# Schematic.net
KiCad netlist of a schematic drawn in Altium Designer
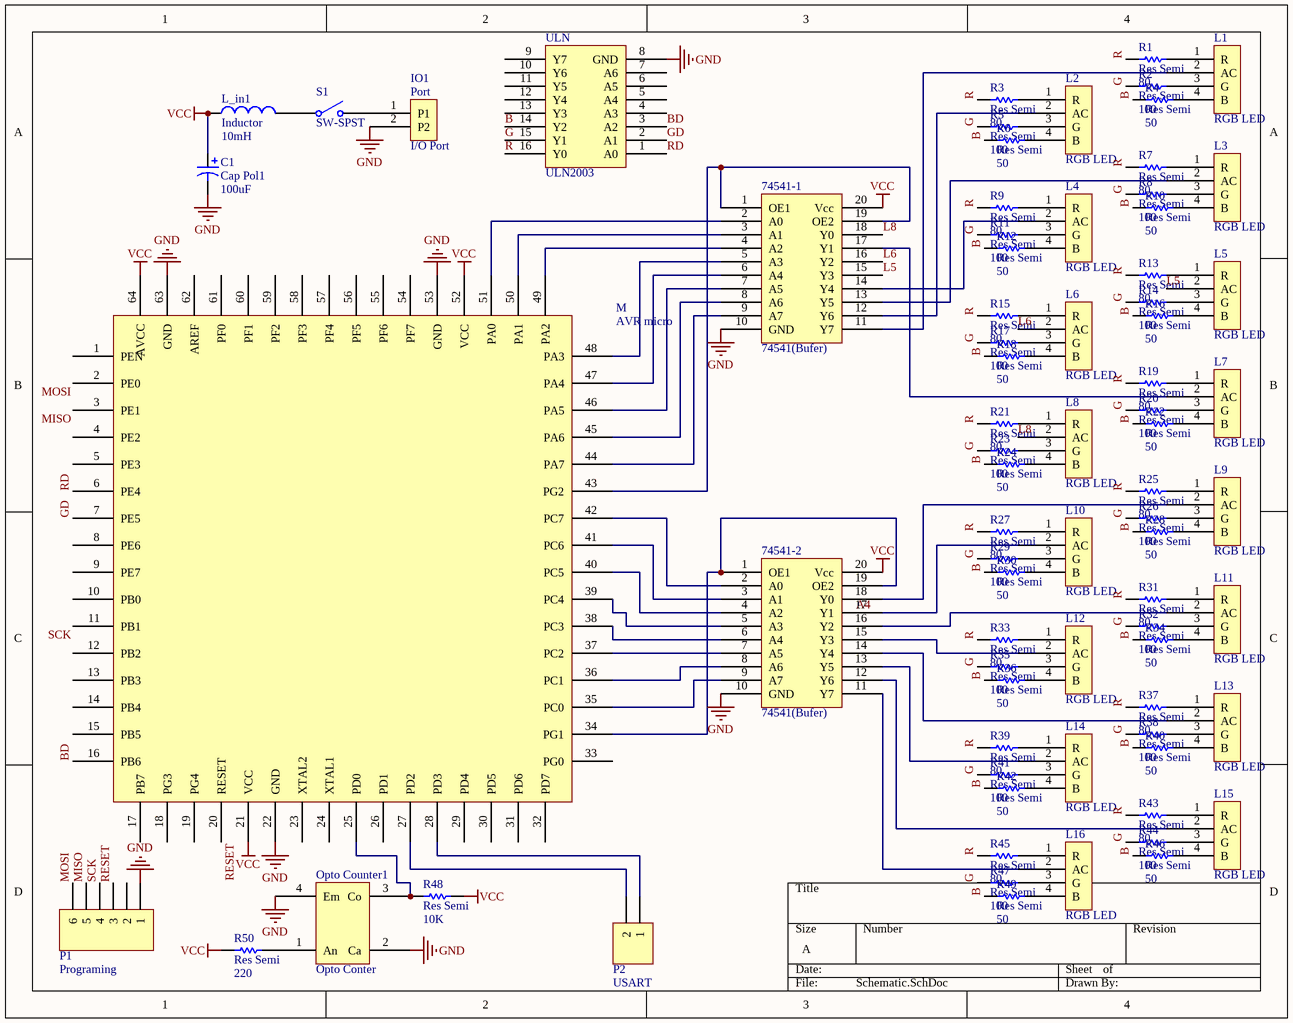
[diagram p0: Schematic.SchDoc]

(export (version "E")
  (design (tool "Eeschema 10.0.6"))
  (components
    (comp (ref "74541-1")
      (value "74541(Bufer)")
      (footprint "SOT146-1")
      (libsource (lib "Schematic Library") (part "74541(Bufer)"))
    )
    (comp (ref "74541-2")
      (value "74541(Bufer)")
      (footprint "SOT146-1")
      (libsource (lib "Schematic Library") (part "74541(Bufer)"))
    )
    (comp (ref "C1")
      (value "Cap Pol1")
      (footprint "CAPPR5-5x5")
      (description "Polarized Capacitor (Radial)")
      (fields (field (name "ALTIUM_VALUE") "100uF") (field (name "PUBLISHER") "Altium Limited"))
      (libsource (lib "Miscellaneous Devices") (part "Cap Pol1"))
    )
    (comp (ref "IO1")
      (value "I/O Port")
      (footprint "I/O")
      (libsource (lib "Schematic Library") (part "I/O Port"))
    )
    (comp (ref "L1")
      (value "RGB LED")
      (footprint "RGB LED")
      (libsource (lib "Schematic Library") (part "RGB LED"))
    )
    (comp (ref "L2")
      (value "RGB LED")
      (footprint "RGB LED")
      (libsource (lib "Schematic Library") (part "RGB LED"))
    )
    (comp (ref "L3")
      (value "RGB LED")
      (footprint "RGB LED")
      (libsource (lib "Schematic Library") (part "RGB LED"))
    )
    (comp (ref "L4")
      (value "RGB LED")
      (footprint "RGB LED")
      (libsource (lib "Schematic Library") (part "RGB LED"))
    )
    (comp (ref "L5")
      (value "RGB LED")
      (footprint "RGB LED")
      (libsource (lib "Schematic Library") (part "RGB LED"))
    )
    (comp (ref "L6")
      (value "RGB LED")
      (footprint "RGB LED")
      (libsource (lib "Schematic Library") (part "RGB LED"))
    )
    (comp (ref "L7")
      (value "RGB LED")
      (footprint "RGB LED")
      (libsource (lib "Schematic Library") (part "RGB LED"))
    )
    (comp (ref "L8")
      (value "RGB LED")
      (footprint "RGB LED")
      (libsource (lib "Schematic Library") (part "RGB LED"))
    )
    (comp (ref "L9")
      (value "RGB LED")
      (footprint "RGB LED")
      (libsource (lib "Schematic Library") (part "RGB LED"))
    )
    (comp (ref "L10")
      (value "RGB LED")
      (footprint "RGB LED")
      (libsource (lib "Schematic Library") (part "RGB LED"))
    )
    (comp (ref "L11")
      (value "RGB LED")
      (footprint "RGB LED")
      (libsource (lib "Schematic Library") (part "RGB LED"))
    )
    (comp (ref "L12")
      (value "RGB LED")
      (footprint "RGB LED")
      (libsource (lib "Schematic Library") (part "RGB LED"))
    )
    (comp (ref "L13")
      (value "RGB LED")
      (footprint "RGB LED")
      (libsource (lib "Schematic Library") (part "RGB LED"))
    )
    (comp (ref "L14")
      (value "RGB LED")
      (footprint "RGB LED")
      (libsource (lib "Schematic Library") (part "RGB LED"))
    )
    (comp (ref "L15")
      (value "RGB LED")
      (footprint "RGB LED")
      (libsource (lib "Schematic Library") (part "RGB LED"))
    )
    (comp (ref "L16")
      (value "RGB LED")
      (footprint "RGB LED")
      (libsource (lib "Schematic Library") (part "RGB LED"))
    )
    (comp (ref "L_in1")
      (value "Inductor")
      (footprint "AXIAL-0.8")
      (fields (field (name "ALTIUM_VALUE") "10mH") (field (name "PUBLISHER") "Altium Limited"))
      (libsource (lib "Miscellaneous Devices") (part "Inductor"))
    )
    (comp (ref "M")
      (value "AVR micro")
      (footprint "64A_M")
      (libsource (lib "Schematic Library") (part "ATmega64"))
    )
    (comp (ref "Opto Counter1")
      (value "Opto Conter")
      (footprint "Opto Counter")
      (libsource (lib "Schematic Library") (part "Opto Counter"))
    )
    (comp (ref "P1")
      (value "Programing")
      (footprint "HDR1X6")
      (description "Header, 6-Pin")
      (fields (field (name "PUBLISHER") "Altium Limited"))
      (libsource (lib "Miscellaneous Connectors") (part "Header 6"))
    )
    (comp (ref "P2")
      (value "USART")
      (footprint "HDR1X2")
      (description "Header, 2-Pin")
      (fields (field (name "PUBLISHER") "Altium Limited"))
      (libsource (lib "Miscellaneous Connectors") (part "Header 2"))
    )
    (comp (ref "R1")
      (value "Res Semi")
      (footprint "RESC2012L")
      (description "Semiconductor Resistor")
      (fields (field (name "ALTIUM_VALUE") "80") (field (name "PUBLISHER") "Altium Limited"))
      (libsource (lib "Miscellaneous Devices") (part "Res Semi"))
    )
    (comp (ref "R2")
      (value "Res Semi")
      (footprint "RESC2012L")
      (description "Semiconductor Resistor")
      (fields (field (name "ALTIUM_VALUE") "100") (field (name "PUBLISHER") "Altium Limited"))
      (libsource (lib "Miscellaneous Devices") (part "Res Semi"))
    )
    (comp (ref "R3")
      (value "Res Semi")
      (footprint "RESC2012L")
      (description "Semiconductor Resistor")
      (fields (field (name "ALTIUM_VALUE") "80") (field (name "PUBLISHER") "Altium Limited"))
      (libsource (lib "Miscellaneous Devices") (part "Res Semi"))
    )
    (comp (ref "R4")
      (value "Res Semi")
      (footprint "RESC2012L")
      (description "Semiconductor Resistor")
      (fields (field (name "ALTIUM_VALUE") "50") (field (name "PUBLISHER") "Altium Limited"))
      (libsource (lib "Miscellaneous Devices") (part "Res Semi"))
    )
    (comp (ref "R5")
      (value "Res Semi")
      (footprint "RESC2012L")
      (description "Semiconductor Resistor")
      (fields (field (name "ALTIUM_VALUE") "100") (field (name "PUBLISHER") "Altium Limited"))
      (libsource (lib "Miscellaneous Devices") (part "Res Semi"))
    )
    (comp (ref "R6")
      (value "Res Semi")
      (footprint "RESC2012L")
      (description "Semiconductor Resistor")
      (fields (field (name "ALTIUM_VALUE") "50") (field (name "PUBLISHER") "Altium Limited"))
      (libsource (lib "Miscellaneous Devices") (part "Res Semi"))
    )
    (comp (ref "R7")
      (value "Res Semi")
      (footprint "RESC2012L")
      (description "Semiconductor Resistor")
      (fields (field (name "ALTIUM_VALUE") "80") (field (name "PUBLISHER") "Altium Limited"))
      (libsource (lib "Miscellaneous Devices") (part "Res Semi"))
    )
    (comp (ref "R8")
      (value "Res Semi")
      (footprint "RESC2012L")
      (description "Semiconductor Resistor")
      (fields (field (name "ALTIUM_VALUE") "100") (field (name "PUBLISHER") "Altium Limited"))
      (libsource (lib "Miscellaneous Devices") (part "Res Semi"))
    )
    (comp (ref "R9")
      (value "Res Semi")
      (footprint "RESC2012L")
      (description "Semiconductor Resistor")
      (fields (field (name "ALTIUM_VALUE") "80") (field (name "PUBLISHER") "Altium Limited"))
      (libsource (lib "Miscellaneous Devices") (part "Res Semi"))
    )
    (comp (ref "R10")
      (value "Res Semi")
      (footprint "RESC2012L")
      (description "Semiconductor Resistor")
      (fields (field (name "ALTIUM_VALUE") "50") (field (name "PUBLISHER") "Altium Limited"))
      (libsource (lib "Miscellaneous Devices") (part "Res Semi"))
    )
    (comp (ref "R11")
      (value "Res Semi")
      (footprint "RESC2012L")
      (description "Semiconductor Resistor")
      (fields (field (name "ALTIUM_VALUE") "100") (field (name "PUBLISHER") "Altium Limited"))
      (libsource (lib "Miscellaneous Devices") (part "Res Semi"))
    )
    (comp (ref "R12")
      (value "Res Semi")
      (footprint "RESC2012L")
      (description "Semiconductor Resistor")
      (fields (field (name "ALTIUM_VALUE") "50") (field (name "PUBLISHER") "Altium Limited"))
      (libsource (lib "Miscellaneous Devices") (part "Res Semi"))
    )
    (comp (ref "R13")
      (value "Res Semi")
      (footprint "RESC2012L")
      (description "Semiconductor Resistor")
      (fields (field (name "ALTIUM_VALUE") "80") (field (name "PUBLISHER") "Altium Limited"))
      (libsource (lib "Miscellaneous Devices") (part "Res Semi"))
    )
    (comp (ref "R14")
      (value "Res Semi")
      (footprint "RESC2012L")
      (description "Semiconductor Resistor")
      (fields (field (name "ALTIUM_VALUE") "100") (field (name "PUBLISHER") "Altium Limited"))
      (libsource (lib "Miscellaneous Devices") (part "Res Semi"))
    )
    (comp (ref "R15")
      (value "Res Semi")
      (footprint "RESC2012L")
      (description "Semiconductor Resistor")
      (fields (field (name "ALTIUM_VALUE") "80") (field (name "PUBLISHER") "Altium Limited"))
      (libsource (lib "Miscellaneous Devices") (part "Res Semi"))
    )
    (comp (ref "R16")
      (value "Res Semi")
      (footprint "RESC2012L")
      (description "Semiconductor Resistor")
      (fields (field (name "ALTIUM_VALUE") "50") (field (name "PUBLISHER") "Altium Limited"))
      (libsource (lib "Miscellaneous Devices") (part "Res Semi"))
    )
    (comp (ref "R17")
      (value "Res Semi")
      (footprint "RESC2012L")
      (description "Semiconductor Resistor")
      (fields (field (name "ALTIUM_VALUE") "100") (field (name "PUBLISHER") "Altium Limited"))
      (libsource (lib "Miscellaneous Devices") (part "Res Semi"))
    )
    (comp (ref "R18")
      (value "Res Semi")
      (footprint "RESC2012L")
      (description "Semiconductor Resistor")
      (fields (field (name "ALTIUM_VALUE") "50") (field (name "PUBLISHER") "Altium Limited"))
      (libsource (lib "Miscellaneous Devices") (part "Res Semi"))
    )
    (comp (ref "R19")
      (value "Res Semi")
      (footprint "RESC2012L")
      (description "Semiconductor Resistor")
      (fields (field (name "ALTIUM_VALUE") "80") (field (name "PUBLISHER") "Altium Limited"))
      (libsource (lib "Miscellaneous Devices") (part "Res Semi"))
    )
    (comp (ref "R20")
      (value "Res Semi")
      (footprint "RESC2012L")
      (description "Semiconductor Resistor")
      (fields (field (name "ALTIUM_VALUE") "100") (field (name "PUBLISHER") "Altium Limited"))
      (libsource (lib "Miscellaneous Devices") (part "Res Semi"))
    )
    (comp (ref "R21")
      (value "Res Semi")
      (footprint "RESC2012L")
      (description "Semiconductor Resistor")
      (fields (field (name "ALTIUM_VALUE") "80") (field (name "PUBLISHER") "Altium Limited"))
      (libsource (lib "Miscellaneous Devices") (part "Res Semi"))
    )
    (comp (ref "R22")
      (value "Res Semi")
      (footprint "RESC2012L")
      (description "Semiconductor Resistor")
      (fields (field (name "ALTIUM_VALUE") "50") (field (name "PUBLISHER") "Altium Limited"))
      (libsource (lib "Miscellaneous Devices") (part "Res Semi"))
    )
    (comp (ref "R23")
      (value "Res Semi")
      (footprint "RESC2012L")
      (description "Semiconductor Resistor")
      (fields (field (name "ALTIUM_VALUE") "100") (field (name "PUBLISHER") "Altium Limited"))
      (libsource (lib "Miscellaneous Devices") (part "Res Semi"))
    )
    (comp (ref "R24")
      (value "Res Semi")
      (footprint "RESC2012L")
      (description "Semiconductor Resistor")
      (fields (field (name "ALTIUM_VALUE") "50") (field (name "PUBLISHER") "Altium Limited"))
      (libsource (lib "Miscellaneous Devices") (part "Res Semi"))
    )
    (comp (ref "R25")
      (value "Res Semi")
      (footprint "RESC2012L")
      (description "Semiconductor Resistor")
      (fields (field (name "ALTIUM_VALUE") "80") (field (name "PUBLISHER") "Altium Limited"))
      (libsource (lib "Miscellaneous Devices") (part "Res Semi"))
    )
    (comp (ref "R26")
      (value "Res Semi")
      (footprint "RESC2012L")
      (description "Semiconductor Resistor")
      (fields (field (name "ALTIUM_VALUE") "100") (field (name "PUBLISHER") "Altium Limited"))
      (libsource (lib "Miscellaneous Devices") (part "Res Semi"))
    )
    (comp (ref "R27")
      (value "Res Semi")
      (footprint "RESC2012L")
      (description "Semiconductor Resistor")
      (fields (field (name "ALTIUM_VALUE") "80") (field (name "PUBLISHER") "Altium Limited"))
      (libsource (lib "Miscellaneous Devices") (part "Res Semi"))
    )
    (comp (ref "R28")
      (value "Res Semi")
      (footprint "RESC2012L")
      (description "Semiconductor Resistor")
      (fields (field (name "ALTIUM_VALUE") "50") (field (name "PUBLISHER") "Altium Limited"))
      (libsource (lib "Miscellaneous Devices") (part "Res Semi"))
    )
    (comp (ref "R29")
      (value "Res Semi")
      (footprint "RESC2012L")
      (description "Semiconductor Resistor")
      (fields (field (name "ALTIUM_VALUE") "100") (field (name "PUBLISHER") "Altium Limited"))
      (libsource (lib "Miscellaneous Devices") (part "Res Semi"))
    )
    (comp (ref "R30")
      (value "Res Semi")
      (footprint "RESC2012L")
      (description "Semiconductor Resistor")
      (fields (field (name "ALTIUM_VALUE") "50") (field (name "PUBLISHER") "Altium Limited"))
      (libsource (lib "Miscellaneous Devices") (part "Res Semi"))
    )
    (comp (ref "R31")
      (value "Res Semi")
      (footprint "RESC2012L")
      (description "Semiconductor Resistor")
      (fields (field (name "ALTIUM_VALUE") "80") (field (name "PUBLISHER") "Altium Limited"))
      (libsource (lib "Miscellaneous Devices") (part "Res Semi"))
    )
    (comp (ref "R32")
      (value "Res Semi")
      (footprint "RESC2012L")
      (description "Semiconductor Resistor")
      (fields (field (name "ALTIUM_VALUE") "100") (field (name "PUBLISHER") "Altium Limited"))
      (libsource (lib "Miscellaneous Devices") (part "Res Semi"))
    )
    (comp (ref "R33")
      (value "Res Semi")
      (footprint "RESC2012L")
      (description "Semiconductor Resistor")
      (fields (field (name "ALTIUM_VALUE") "80") (field (name "PUBLISHER") "Altium Limited"))
      (libsource (lib "Miscellaneous Devices") (part "Res Semi"))
    )
    (comp (ref "R34")
      (value "Res Semi")
      (footprint "RESC2012L")
      (description "Semiconductor Resistor")
      (fields (field (name "ALTIUM_VALUE") "50") (field (name "PUBLISHER") "Altium Limited"))
      (libsource (lib "Miscellaneous Devices") (part "Res Semi"))
    )
    (comp (ref "R35")
      (value "Res Semi")
      (footprint "RESC2012L")
      (description "Semiconductor Resistor")
      (fields (field (name "ALTIUM_VALUE") "100") (field (name "PUBLISHER") "Altium Limited"))
      (libsource (lib "Miscellaneous Devices") (part "Res Semi"))
    )
    (comp (ref "R36")
      (value "Res Semi")
      (footprint "RESC2012L")
      (description "Semiconductor Resistor")
      (fields (field (name "ALTIUM_VALUE") "50") (field (name "PUBLISHER") "Altium Limited"))
      (libsource (lib "Miscellaneous Devices") (part "Res Semi"))
    )
    (comp (ref "R37")
      (value "Res Semi")
      (footprint "RESC2012L")
      (description "Semiconductor Resistor")
      (fields (field (name "ALTIUM_VALUE") "80") (field (name "PUBLISHER") "Altium Limited"))
      (libsource (lib "Miscellaneous Devices") (part "Res Semi"))
    )
    (comp (ref "R38")
      (value "Res Semi")
      (footprint "RESC2012L")
      (description "Semiconductor Resistor")
      (fields (field (name "ALTIUM_VALUE") "100") (field (name "PUBLISHER") "Altium Limited"))
      (libsource (lib "Miscellaneous Devices") (part "Res Semi"))
    )
    (comp (ref "R39")
      (value "Res Semi")
      (footprint "RESC2012L")
      (description "Semiconductor Resistor")
      (fields (field (name "ALTIUM_VALUE") "80") (field (name "PUBLISHER") "Altium Limited"))
      (libsource (lib "Miscellaneous Devices") (part "Res Semi"))
    )
    (comp (ref "R40")
      (value "Res Semi")
      (footprint "RESC2012L")
      (description "Semiconductor Resistor")
      (fields (field (name "ALTIUM_VALUE") "50") (field (name "PUBLISHER") "Altium Limited"))
      (libsource (lib "Miscellaneous Devices") (part "Res Semi"))
    )
    (comp (ref "R41")
      (value "Res Semi")
      (footprint "RESC2012L")
      (description "Semiconductor Resistor")
      (fields (field (name "ALTIUM_VALUE") "100") (field (name "PUBLISHER") "Altium Limited"))
      (libsource (lib "Miscellaneous Devices") (part "Res Semi"))
    )
    (comp (ref "R42")
      (value "Res Semi")
      (footprint "RESC2012L")
      (description "Semiconductor Resistor")
      (fields (field (name "ALTIUM_VALUE") "50") (field (name "PUBLISHER") "Altium Limited"))
      (libsource (lib "Miscellaneous Devices") (part "Res Semi"))
    )
    (comp (ref "R43")
      (value "Res Semi")
      (footprint "RESC2012L")
      (description "Semiconductor Resistor")
      (fields (field (name "ALTIUM_VALUE") "80") (field (name "PUBLISHER") "Altium Limited"))
      (libsource (lib "Miscellaneous Devices") (part "Res Semi"))
    )
    (comp (ref "R44")
      (value "Res Semi")
      (footprint "RESC2012L")
      (description "Semiconductor Resistor")
      (fields (field (name "ALTIUM_VALUE") "100") (field (name "PUBLISHER") "Altium Limited"))
      (libsource (lib "Miscellaneous Devices") (part "Res Semi"))
    )
    (comp (ref "R45")
      (value "Res Semi")
      (footprint "RESC2012L")
      (description "Semiconductor Resistor")
      (fields (field (name "ALTIUM_VALUE") "80") (field (name "PUBLISHER") "Altium Limited"))
      (libsource (lib "Miscellaneous Devices") (part "Res Semi"))
    )
    (comp (ref "R46")
      (value "Res Semi")
      (footprint "RESC2012L")
      (description "Semiconductor Resistor")
      (fields (field (name "ALTIUM_VALUE") "50") (field (name "PUBLISHER") "Altium Limited"))
      (libsource (lib "Miscellaneous Devices") (part "Res Semi"))
    )
    (comp (ref "R47")
      (value "Res Semi")
      (footprint "RESC2012L")
      (description "Semiconductor Resistor")
      (fields (field (name "ALTIUM_VALUE") "100") (field (name "PUBLISHER") "Altium Limited"))
      (libsource (lib "Miscellaneous Devices") (part "Res Semi"))
    )
    (comp (ref "R48")
      (value "Res Semi")
      (footprint "RESC2012L")
      (description "Semiconductor Resistor")
      (fields (field (name "ALTIUM_VALUE") "10K") (field (name "PUBLISHER") "Altium Limited"))
      (libsource (lib "Miscellaneous Devices") (part "Res Semi"))
    )
    (comp (ref "R49")
      (value "Res Semi")
      (footprint "RESC2012L")
      (description "Semiconductor Resistor")
      (fields (field (name "ALTIUM_VALUE") "50") (field (name "PUBLISHER") "Altium Limited"))
      (libsource (lib "Miscellaneous Devices") (part "Res Semi"))
    )
    (comp (ref "R50")
      (value "Res Semi")
      (footprint "RESC2012L")
      (description "Semiconductor Resistor")
      (fields (field (name "ALTIUM_VALUE") "220") (field (name "PUBLISHER") "Altium Limited"))
      (libsource (lib "Miscellaneous Devices") (part "Res Semi"))
    )
    (comp (ref "S1")
      (value "SW-SPST")
      (footprint "SPST-2")
      (description "Single-Pole, Single-Throw Switch")
      (fields (field (name "PUBLISHER") "Altium Limited"))
      (libsource (lib "Miscellaneous Devices") (part "SW-SPST"))
    )
    (comp (ref "ULN")
      (value "ULN2003")
      (footprint "A16")
      (libsource (lib "Schematic Library") (part "ULN2003"))
    )
  )
  (nets
    (net (code "2") (name "/B") (class "Default")
      (node (ref "R10") (pin "1") (pinfunction "1_1") (pintype "passive"))
      (node (ref "R12") (pin "1") (pinfunction "1_1") (pintype "passive"))
      (node (ref "R16") (pin "1") (pinfunction "1_1") (pintype "passive"))
      (node (ref "R18") (pin "1") (pinfunction "1_1") (pintype "passive"))
      (node (ref "R22") (pin "1") (pinfunction "1_1") (pintype "passive"))
      (node (ref "R24") (pin "1") (pinfunction "1_1") (pintype "passive"))
      (node (ref "R28") (pin "1") (pinfunction "1_1") (pintype "passive"))
      (node (ref "R30") (pin "1") (pinfunction "1_1") (pintype "passive"))
      (node (ref "R34") (pin "1") (pinfunction "1_1") (pintype "passive"))
      (node (ref "R36") (pin "1") (pinfunction "1_1") (pintype "passive"))
      (node (ref "R4") (pin "1") (pinfunction "1_1") (pintype "passive"))
      (node (ref "R40") (pin "1") (pinfunction "1_1") (pintype "passive"))
      (node (ref "R42") (pin "1") (pinfunction "1_1") (pintype "passive"))
      (node (ref "R46") (pin "1") (pinfunction "1_1") (pintype "passive"))
      (node (ref "R49") (pin "1") (pinfunction "1_1") (pintype "passive"))
      (node (ref "R6") (pin "1") (pinfunction "1_1") (pintype "passive"))
      (node (ref "ULN") (pin "14") (pinfunction "Y2_14") (pintype "passive"))
    )
    (net (code "3") (name "/BD") (class "Default")
      (node (ref "M") (pin "16") (pinfunction "PB6_16") (pintype "passive"))
      (node (ref "ULN") (pin "3") (pinfunction "A2_3") (pintype "passive"))
    )
    (net (code "4") (name "/G") (class "Default")
      (node (ref "R11") (pin "1") (pinfunction "1_1") (pintype "passive"))
      (node (ref "R14") (pin "1") (pinfunction "1_1") (pintype "passive"))
      (node (ref "R17") (pin "1") (pinfunction "1_1") (pintype "passive"))
      (node (ref "R2") (pin "1") (pinfunction "1_1") (pintype "passive"))
      (node (ref "R20") (pin "1") (pinfunction "1_1") (pintype "passive"))
      (node (ref "R23") (pin "1") (pinfunction "1_1") (pintype "passive"))
      (node (ref "R26") (pin "1") (pinfunction "1_1") (pintype "passive"))
      (node (ref "R29") (pin "1") (pinfunction "1_1") (pintype "passive"))
      (node (ref "R32") (pin "1") (pinfunction "1_1") (pintype "passive"))
      (node (ref "R35") (pin "1") (pinfunction "1_1") (pintype "passive"))
      (node (ref "R38") (pin "1") (pinfunction "1_1") (pintype "passive"))
      (node (ref "R41") (pin "1") (pinfunction "1_1") (pintype "passive"))
      (node (ref "R44") (pin "1") (pinfunction "1_1") (pintype "passive"))
      (node (ref "R47") (pin "1") (pinfunction "1_1") (pintype "passive"))
      (node (ref "R5") (pin "1") (pinfunction "1_1") (pintype "passive"))
      (node (ref "R8") (pin "1") (pinfunction "1_1") (pintype "passive"))
      (node (ref "ULN") (pin "15") (pinfunction "Y1_15") (pintype "passive"))
    )
    (net (code "5") (name "/GD") (class "Default")
      (node (ref "M") (pin "7") (pinfunction "PE5_7") (pintype "passive"))
      (node (ref "ULN") (pin "2") (pinfunction "A1_2") (pintype "passive"))
    )
    (net (code "6") (name "/L5") (class "Default")
      (node (ref "74541-1") (pin "15") (pinfunction "Y3_15") (pintype "passive"))
      (node (ref "L5") (pin "2") (pinfunction "AC_2") (pintype "passive"))
    )
    (net (code "7") (name "/L6") (class "Default")
      (node (ref "74541-1") (pin "16") (pinfunction "Y2_16") (pintype "passive"))
      (node (ref "L6") (pin "2") (pinfunction "AC_2") (pintype "passive"))
    )
    (net (code "8") (name "/L8") (class "Default")
      (node (ref "74541-1") (pin "18") (pinfunction "Y0_18") (pintype "passive"))
      (node (ref "L8") (pin "2") (pinfunction "AC_2") (pintype "passive"))
    )
    (net (code "9") (name "/MISO") (class "Default")
      (node (ref "M") (pin "3") (pinfunction "PE1_3") (pintype "passive"))
      (node (ref "P1") (pin "5") (pinfunction "5_5") (pintype "passive"))
    )
    (net (code "10") (name "/MOSI") (class "Default")
      (node (ref "M") (pin "2") (pinfunction "PE0_2") (pintype "passive"))
      (node (ref "P1") (pin "6") (pinfunction "6_6") (pintype "passive"))
    )
    (net (code "11") (name "/R") (class "Default")
      (node (ref "R1") (pin "1") (pinfunction "1_1") (pintype "passive"))
      (node (ref "R13") (pin "1") (pinfunction "1_1") (pintype "passive"))
      (node (ref "R15") (pin "1") (pinfunction "1_1") (pintype "passive"))
      (node (ref "R19") (pin "1") (pinfunction "1_1") (pintype "passive"))
      (node (ref "R21") (pin "1") (pinfunction "1_1") (pintype "passive"))
      (node (ref "R25") (pin "1") (pinfunction "1_1") (pintype "passive"))
      (node (ref "R27") (pin "1") (pinfunction "1_1") (pintype "passive"))
      (node (ref "R3") (pin "1") (pinfunction "1_1") (pintype "passive"))
      (node (ref "R31") (pin "1") (pinfunction "1_1") (pintype "passive"))
      (node (ref "R33") (pin "1") (pinfunction "1_1") (pintype "passive"))
      (node (ref "R37") (pin "1") (pinfunction "1_1") (pintype "passive"))
      (node (ref "R39") (pin "1") (pinfunction "1_1") (pintype "passive"))
      (node (ref "R43") (pin "1") (pinfunction "1_1") (pintype "passive"))
      (node (ref "R45") (pin "1") (pinfunction "1_1") (pintype "passive"))
      (node (ref "R7") (pin "1") (pinfunction "1_1") (pintype "passive"))
      (node (ref "R9") (pin "1") (pinfunction "1_1") (pintype "passive"))
      (node (ref "ULN") (pin "16") (pinfunction "Y0_16") (pintype "passive"))
    )
    (net (code "12") (name "/RD") (class "Default")
      (node (ref "M") (pin "6") (pinfunction "PE4_6") (pintype "passive"))
      (node (ref "ULN") (pin "1") (pinfunction "A0_1") (pintype "passive"))
    )
    (net (code "13") (name "/RESET") (class "Default")
      (node (ref "M") (pin "20") (pinfunction "RESET_20") (pintype "passive"))
      (node (ref "P1") (pin "3") (pinfunction "3_3") (pintype "passive"))
    )
    (net (code "14") (name "/SCK") (class "Default")
      (node (ref "M") (pin "11") (pinfunction "PB1_11") (pintype "passive"))
      (node (ref "P1") (pin "4") (pinfunction "4_4") (pintype "passive"))
    )
    (net (code "15") (name "GND") (class "Default")
      (node (ref "74541-1") (pin "10") (pinfunction "GND_10") (pintype "passive"))
      (node (ref "74541-2") (pin "10") (pinfunction "GND_10") (pintype "passive"))
      (node (ref "C1") (pin "2") (pinfunction "2_2") (pintype "passive"))
      (node (ref "IO1") (pin "2") (pinfunction "P2_2") (pintype "passive"))
      (node (ref "M") (pin "22") (pinfunction "GND_22") (pintype "power_in"))
      (node (ref "M") (pin "53") (pinfunction "GND_53") (pintype "power_in"))
      (node (ref "M") (pin "63") (pinfunction "GND_63") (pintype "power_in"))
      (node (ref "Opto Counter1") (pin "2") (pinfunction "Ca_2") (pintype "passive"))
      (node (ref "Opto Counter1") (pin "4") (pinfunction "Em_4") (pintype "passive"))
      (node (ref "P1") (pin "1") (pinfunction "1_1") (pintype "passive"))
      (node (ref "ULN") (pin "8") (pinfunction "GND_8") (pintype "passive"))
    )
    (net (code "16") (name "Net-(74541-1-A0)") (class "Default")
      (node (ref "74541-1") (pin "2") (pinfunction "A0_2") (pintype "passive"))
      (node (ref "M") (pin "51") (pinfunction "PA0_51") (pintype "passive"))
    )
    (net (code "17") (name "Net-(74541-1-A1)") (class "Default")
      (node (ref "74541-1") (pin "3") (pinfunction "A1_3") (pintype "passive"))
      (node (ref "M") (pin "50") (pinfunction "PA1_50") (pintype "passive"))
    )
    (net (code "18") (name "Net-(74541-1-A2)") (class "Default")
      (node (ref "74541-1") (pin "4") (pinfunction "A2_4") (pintype "passive"))
      (node (ref "M") (pin "49") (pinfunction "PA2_49") (pintype "passive"))
    )
    (net (code "19") (name "Net-(74541-1-A3)") (class "Default")
      (node (ref "74541-1") (pin "5") (pinfunction "A3_5") (pintype "passive"))
      (node (ref "M") (pin "48") (pinfunction "PA3_48") (pintype "passive"))
    )
    (net (code "20") (name "Net-(74541-1-A4)") (class "Default")
      (node (ref "74541-1") (pin "6") (pinfunction "A4_6") (pintype "passive"))
      (node (ref "M") (pin "47") (pinfunction "PA4_47") (pintype "passive"))
    )
    (net (code "21") (name "Net-(74541-1-A5)") (class "Default")
      (node (ref "74541-1") (pin "7") (pinfunction "A5_7") (pintype "passive"))
      (node (ref "M") (pin "46") (pinfunction "PA5_46") (pintype "passive"))
    )
    (net (code "22") (name "Net-(74541-1-A6)") (class "Default")
      (node (ref "74541-1") (pin "8") (pinfunction "A6_8") (pintype "passive"))
      (node (ref "M") (pin "45") (pinfunction "PA6_45") (pintype "passive"))
    )
    (net (code "23") (name "Net-(74541-1-A7)") (class "Default")
      (node (ref "74541-1") (pin "9") (pinfunction "A7_9") (pintype "passive"))
      (node (ref "M") (pin "44") (pinfunction "PA7_44") (pintype "passive"))
    )
    (net (code "24") (name "Net-(74541-1-OE1)") (class "Default")
      (node (ref "74541-1") (pin "1") (pinfunction "OE1_1") (pintype "passive"))
      (node (ref "74541-1") (pin "19") (pinfunction "OE2_19") (pintype "passive"))
      (node (ref "M") (pin "43") (pinfunction "PG2_43") (pintype "passive"))
    )
    (net (code "25") (name "Net-(74541-1-Y1)") (class "Default")
      (node (ref "74541-1") (pin "17") (pinfunction "Y1_17") (pintype "passive"))
      (node (ref "L7") (pin "2") (pinfunction "AC_2") (pintype "passive"))
    )
    (net (code "26") (name "Net-(74541-1-Y4)") (class "Default")
      (node (ref "74541-1") (pin "14") (pinfunction "Y4_14") (pintype "passive"))
      (node (ref "L4") (pin "2") (pinfunction "AC_2") (pintype "passive"))
    )
    (net (code "27") (name "Net-(74541-1-Y5)") (class "Default")
      (node (ref "74541-1") (pin "13") (pinfunction "Y5_13") (pintype "passive"))
      (node (ref "L3") (pin "2") (pinfunction "AC_2") (pintype "passive"))
    )
    (net (code "28") (name "Net-(74541-1-Y6)") (class "Default")
      (node (ref "74541-1") (pin "12") (pinfunction "Y6_12") (pintype "passive"))
      (node (ref "L2") (pin "2") (pinfunction "AC_2") (pintype "passive"))
    )
    (net (code "29") (name "Net-(74541-1-Y7)") (class "Default")
      (node (ref "74541-1") (pin "11") (pinfunction "Y7_11") (pintype "passive"))
      (node (ref "L1") (pin "2") (pinfunction "AC_2") (pintype "passive"))
    )
    (net (code "30") (name "Net-(74541-2-A0)") (class "Default")
      (node (ref "74541-2") (pin "2") (pinfunction "A0_2") (pintype "passive"))
      (node (ref "M") (pin "42") (pinfunction "PC7_42") (pintype "passive"))
    )
    (net (code "31") (name "Net-(74541-2-A1)") (class "Default")
      (node (ref "74541-2") (pin "3") (pinfunction "A1_3") (pintype "passive"))
      (node (ref "M") (pin "41") (pinfunction "PC6_41") (pintype "passive"))
    )
    (net (code "32") (name "Net-(74541-2-A2)") (class "Default")
      (node (ref "74541-2") (pin "4") (pinfunction "A2_4") (pintype "passive"))
      (node (ref "M") (pin "40") (pinfunction "PC5_40") (pintype "passive"))
    )
    (net (code "33") (name "Net-(74541-2-A3)") (class "Default")
      (node (ref "74541-2") (pin "5") (pinfunction "A3_5") (pintype "passive"))
      (node (ref "M") (pin "39") (pinfunction "PC4_39") (pintype "passive"))
    )
    (net (code "34") (name "Net-(74541-2-A4)") (class "Default")
      (node (ref "74541-2") (pin "6") (pinfunction "A4_6") (pintype "passive"))
      (node (ref "M") (pin "38") (pinfunction "PC3_38") (pintype "passive"))
    )
    (net (code "35") (name "Net-(74541-2-A5)") (class "Default")
      (node (ref "74541-2") (pin "7") (pinfunction "A5_7") (pintype "passive"))
      (node (ref "M") (pin "37") (pinfunction "PC2_37") (pintype "passive"))
    )
    (net (code "36") (name "Net-(74541-2-A6)") (class "Default")
      (node (ref "74541-2") (pin "8") (pinfunction "A6_8") (pintype "passive"))
      (node (ref "M") (pin "36") (pinfunction "PC1_36") (pintype "passive"))
    )
    (net (code "37") (name "Net-(74541-2-A7)") (class "Default")
      (node (ref "74541-2") (pin "9") (pinfunction "A7_9") (pintype "passive"))
      (node (ref "M") (pin "35") (pinfunction "PC0_35") (pintype "passive"))
    )
    (net (code "38") (name "Net-(74541-2-OE1)") (class "Default")
      (node (ref "74541-2") (pin "1") (pinfunction "OE1_1") (pintype "passive"))
      (node (ref "74541-2") (pin "19") (pinfunction "OE2_19") (pintype "passive"))
      (node (ref "M") (pin "34") (pinfunction "PG1_34") (pintype "passive"))
    )
    (net (code "39") (name "Net-(74541-2-Y0)") (class "Default")
      (node (ref "74541-2") (pin "18") (pinfunction "Y0_18") (pintype "passive"))
      (node (ref "L9") (pin "2") (pinfunction "AC_2") (pintype "passive"))
    )
    (net (code "40") (name "Net-(74541-2-Y1)") (class "Default")
      (node (ref "74541-2") (pin "17") (pinfunction "Y1_17") (pintype "passive"))
      (node (ref "L10") (pin "2") (pinfunction "AC_2") (pintype "passive"))
    )
    (net (code "41") (name "Net-(74541-2-Y2)") (class "Default")
      (node (ref "74541-2") (pin "16") (pinfunction "Y2_16") (pintype "passive"))
      (node (ref "L11") (pin "2") (pinfunction "AC_2") (pintype "passive"))
    )
    (net (code "42") (name "Net-(74541-2-Y3)") (class "Default")
      (node (ref "74541-2") (pin "15") (pinfunction "Y3_15") (pintype "passive"))
      (node (ref "L12") (pin "2") (pinfunction "AC_2") (pintype "passive"))
    )
    (net (code "43") (name "Net-(74541-2-Y4)") (class "Default")
      (node (ref "74541-2") (pin "14") (pinfunction "Y4_14") (pintype "passive"))
      (node (ref "L13") (pin "2") (pinfunction "AC_2") (pintype "passive"))
    )
    (net (code "44") (name "Net-(74541-2-Y5)") (class "Default")
      (node (ref "74541-2") (pin "13") (pinfunction "Y5_13") (pintype "passive"))
      (node (ref "L14") (pin "2") (pinfunction "AC_2") (pintype "passive"))
    )
    (net (code "45") (name "Net-(74541-2-Y6)") (class "Default")
      (node (ref "74541-2") (pin "12") (pinfunction "Y6_12") (pintype "passive"))
      (node (ref "L15") (pin "2") (pinfunction "AC_2") (pintype "passive"))
    )
    (net (code "46") (name "Net-(74541-2-Y7)") (class "Default")
      (node (ref "74541-2") (pin "11") (pinfunction "Y7_11") (pintype "passive"))
      (node (ref "L16") (pin "2") (pinfunction "AC_2") (pintype "passive"))
    )
    (net (code "47") (name "Net-(IO1-P1)") (class "Default")
      (node (ref "IO1") (pin "1") (pinfunction "P1_1") (pintype "passive"))
      (node (ref "S1") (pin "2") (pinfunction "NO_2") (pintype "passive"))
    )
    (net (code "48") (name "Net-(L1-B)") (class "Default")
      (node (ref "L1") (pin "4") (pinfunction "B_4") (pintype "passive"))
      (node (ref "R4") (pin "2") (pinfunction "2_2") (pintype "passive"))
    )
    (net (code "49") (name "Net-(L1-G)") (class "Default")
      (node (ref "L1") (pin "3") (pinfunction "G_3") (pintype "passive"))
      (node (ref "R2") (pin "2") (pinfunction "2_2") (pintype "passive"))
    )
    (net (code "50") (name "Net-(L1-R)") (class "Default")
      (node (ref "L1") (pin "1") (pinfunction "R_1") (pintype "passive"))
      (node (ref "R1") (pin "2") (pinfunction "2_2") (pintype "passive"))
    )
    (net (code "51") (name "Net-(L2-B)") (class "Default")
      (node (ref "L2") (pin "4") (pinfunction "B_4") (pintype "passive"))
      (node (ref "R6") (pin "2") (pinfunction "2_2") (pintype "passive"))
    )
    (net (code "52") (name "Net-(L2-G)") (class "Default")
      (node (ref "L2") (pin "3") (pinfunction "G_3") (pintype "passive"))
      (node (ref "R5") (pin "2") (pinfunction "2_2") (pintype "passive"))
    )
    (net (code "53") (name "Net-(L2-R)") (class "Default")
      (node (ref "L2") (pin "1") (pinfunction "R_1") (pintype "passive"))
      (node (ref "R3") (pin "2") (pinfunction "2_2") (pintype "passive"))
    )
    (net (code "54") (name "Net-(L3-B)") (class "Default")
      (node (ref "L3") (pin "4") (pinfunction "B_4") (pintype "passive"))
      (node (ref "R10") (pin "2") (pinfunction "2_2") (pintype "passive"))
    )
    (net (code "55") (name "Net-(L3-G)") (class "Default")
      (node (ref "L3") (pin "3") (pinfunction "G_3") (pintype "passive"))
      (node (ref "R8") (pin "2") (pinfunction "2_2") (pintype "passive"))
    )
    (net (code "56") (name "Net-(L3-R)") (class "Default")
      (node (ref "L3") (pin "1") (pinfunction "R_1") (pintype "passive"))
      (node (ref "R7") (pin "2") (pinfunction "2_2") (pintype "passive"))
    )
    (net (code "57") (name "Net-(L4-B)") (class "Default")
      (node (ref "L4") (pin "4") (pinfunction "B_4") (pintype "passive"))
      (node (ref "R12") (pin "2") (pinfunction "2_2") (pintype "passive"))
    )
    (net (code "58") (name "Net-(L4-G)") (class "Default")
      (node (ref "L4") (pin "3") (pinfunction "G_3") (pintype "passive"))
      (node (ref "R11") (pin "2") (pinfunction "2_2") (pintype "passive"))
    )
    (net (code "59") (name "Net-(L4-R)") (class "Default")
      (node (ref "L4") (pin "1") (pinfunction "R_1") (pintype "passive"))
      (node (ref "R9") (pin "2") (pinfunction "2_2") (pintype "passive"))
    )
    (net (code "60") (name "Net-(L5-B)") (class "Default")
      (node (ref "L5") (pin "4") (pinfunction "B_4") (pintype "passive"))
      (node (ref "R16") (pin "2") (pinfunction "2_2") (pintype "passive"))
    )
    (net (code "61") (name "Net-(L5-G)") (class "Default")
      (node (ref "L5") (pin "3") (pinfunction "G_3") (pintype "passive"))
      (node (ref "R14") (pin "2") (pinfunction "2_2") (pintype "passive"))
    )
    (net (code "62") (name "Net-(L5-R)") (class "Default")
      (node (ref "L5") (pin "1") (pinfunction "R_1") (pintype "passive"))
      (node (ref "R13") (pin "2") (pinfunction "2_2") (pintype "passive"))
    )
    (net (code "63") (name "Net-(L6-B)") (class "Default")
      (node (ref "L6") (pin "4") (pinfunction "B_4") (pintype "passive"))
      (node (ref "R18") (pin "2") (pinfunction "2_2") (pintype "passive"))
    )
    (net (code "64") (name "Net-(L6-G)") (class "Default")
      (node (ref "L6") (pin "3") (pinfunction "G_3") (pintype "passive"))
      (node (ref "R17") (pin "2") (pinfunction "2_2") (pintype "passive"))
    )
    (net (code "65") (name "Net-(L6-R)") (class "Default")
      (node (ref "L6") (pin "1") (pinfunction "R_1") (pintype "passive"))
      (node (ref "R15") (pin "2") (pinfunction "2_2") (pintype "passive"))
    )
    (net (code "66") (name "Net-(L7-B)") (class "Default")
      (node (ref "L7") (pin "4") (pinfunction "B_4") (pintype "passive"))
      (node (ref "R22") (pin "2") (pinfunction "2_2") (pintype "passive"))
    )
    (net (code "67") (name "Net-(L7-G)") (class "Default")
      (node (ref "L7") (pin "3") (pinfunction "G_3") (pintype "passive"))
      (node (ref "R20") (pin "2") (pinfunction "2_2") (pintype "passive"))
    )
    (net (code "68") (name "Net-(L7-R)") (class "Default")
      (node (ref "L7") (pin "1") (pinfunction "R_1") (pintype "passive"))
      (node (ref "R19") (pin "2") (pinfunction "2_2") (pintype "passive"))
    )
    (net (code "69") (name "Net-(L8-B)") (class "Default")
      (node (ref "L8") (pin "4") (pinfunction "B_4") (pintype "passive"))
      (node (ref "R24") (pin "2") (pinfunction "2_2") (pintype "passive"))
    )
    (net (code "70") (name "Net-(L8-G)") (class "Default")
      (node (ref "L8") (pin "3") (pinfunction "G_3") (pintype "passive"))
      (node (ref "R23") (pin "2") (pinfunction "2_2") (pintype "passive"))
    )
    (net (code "71") (name "Net-(L8-R)") (class "Default")
      (node (ref "L8") (pin "1") (pinfunction "R_1") (pintype "passive"))
      (node (ref "R21") (pin "2") (pinfunction "2_2") (pintype "passive"))
    )
    (net (code "72") (name "Net-(L9-B)") (class "Default")
      (node (ref "L9") (pin "4") (pinfunction "B_4") (pintype "passive"))
      (node (ref "R28") (pin "2") (pinfunction "2_2") (pintype "passive"))
    )
    (net (code "73") (name "Net-(L9-G)") (class "Default")
      (node (ref "L9") (pin "3") (pinfunction "G_3") (pintype "passive"))
      (node (ref "R26") (pin "2") (pinfunction "2_2") (pintype "passive"))
    )
    (net (code "74") (name "Net-(L9-R)") (class "Default")
      (node (ref "L9") (pin "1") (pinfunction "R_1") (pintype "passive"))
      (node (ref "R25") (pin "2") (pinfunction "2_2") (pintype "passive"))
    )
    (net (code "75") (name "Net-(L10-B)") (class "Default")
      (node (ref "L10") (pin "4") (pinfunction "B_4") (pintype "passive"))
      (node (ref "R30") (pin "2") (pinfunction "2_2") (pintype "passive"))
    )
    (net (code "76") (name "Net-(L10-G)") (class "Default")
      (node (ref "L10") (pin "3") (pinfunction "G_3") (pintype "passive"))
      (node (ref "R29") (pin "2") (pinfunction "2_2") (pintype "passive"))
    )
    (net (code "77") (name "Net-(L10-R)") (class "Default")
      (node (ref "L10") (pin "1") (pinfunction "R_1") (pintype "passive"))
      (node (ref "R27") (pin "2") (pinfunction "2_2") (pintype "passive"))
    )
    (net (code "78") (name "Net-(L11-B)") (class "Default")
      (node (ref "L11") (pin "4") (pinfunction "B_4") (pintype "passive"))
      (node (ref "R34") (pin "2") (pinfunction "2_2") (pintype "passive"))
    )
    (net (code "79") (name "Net-(L11-G)") (class "Default")
      (node (ref "L11") (pin "3") (pinfunction "G_3") (pintype "passive"))
      (node (ref "R32") (pin "2") (pinfunction "2_2") (pintype "passive"))
    )
    (net (code "80") (name "Net-(L11-R)") (class "Default")
      (node (ref "L11") (pin "1") (pinfunction "R_1") (pintype "passive"))
      (node (ref "R31") (pin "2") (pinfunction "2_2") (pintype "passive"))
    )
    (net (code "81") (name "Net-(L12-B)") (class "Default")
      (node (ref "L12") (pin "4") (pinfunction "B_4") (pintype "passive"))
      (node (ref "R36") (pin "2") (pinfunction "2_2") (pintype "passive"))
    )
    (net (code "82") (name "Net-(L12-G)") (class "Default")
      (node (ref "L12") (pin "3") (pinfunction "G_3") (pintype "passive"))
      (node (ref "R35") (pin "2") (pinfunction "2_2") (pintype "passive"))
    )
    (net (code "83") (name "Net-(L12-R)") (class "Default")
      (node (ref "L12") (pin "1") (pinfunction "R_1") (pintype "passive"))
      (node (ref "R33") (pin "2") (pinfunction "2_2") (pintype "passive"))
    )
    (net (code "84") (name "Net-(L13-B)") (class "Default")
      (node (ref "L13") (pin "4") (pinfunction "B_4") (pintype "passive"))
      (node (ref "R40") (pin "2") (pinfunction "2_2") (pintype "passive"))
    )
    (net (code "85") (name "Net-(L13-G)") (class "Default")
      (node (ref "L13") (pin "3") (pinfunction "G_3") (pintype "passive"))
      (node (ref "R38") (pin "2") (pinfunction "2_2") (pintype "passive"))
    )
    (net (code "86") (name "Net-(L13-R)") (class "Default")
      (node (ref "L13") (pin "1") (pinfunction "R_1") (pintype "passive"))
      (node (ref "R37") (pin "2") (pinfunction "2_2") (pintype "passive"))
    )
    (net (code "87") (name "Net-(L14-B)") (class "Default")
      (node (ref "L14") (pin "4") (pinfunction "B_4") (pintype "passive"))
      (node (ref "R42") (pin "2") (pinfunction "2_2") (pintype "passive"))
    )
    (net (code "88") (name "Net-(L14-G)") (class "Default")
      (node (ref "L14") (pin "3") (pinfunction "G_3") (pintype "passive"))
      (node (ref "R41") (pin "2") (pinfunction "2_2") (pintype "passive"))
    )
    (net (code "89") (name "Net-(L14-R)") (class "Default")
      (node (ref "L14") (pin "1") (pinfunction "R_1") (pintype "passive"))
      (node (ref "R39") (pin "2") (pinfunction "2_2") (pintype "passive"))
    )
    (net (code "90") (name "Net-(L15-B)") (class "Default")
      (node (ref "L15") (pin "4") (pinfunction "B_4") (pintype "passive"))
      (node (ref "R46") (pin "2") (pinfunction "2_2") (pintype "passive"))
    )
    (net (code "91") (name "Net-(L15-G)") (class "Default")
      (node (ref "L15") (pin "3") (pinfunction "G_3") (pintype "passive"))
      (node (ref "R44") (pin "2") (pinfunction "2_2") (pintype "passive"))
    )
    (net (code "92") (name "Net-(L15-R)") (class "Default")
      (node (ref "L15") (pin "1") (pinfunction "R_1") (pintype "passive"))
      (node (ref "R43") (pin "2") (pinfunction "2_2") (pintype "passive"))
    )
    (net (code "93") (name "Net-(L16-B)") (class "Default")
      (node (ref "L16") (pin "4") (pinfunction "B_4") (pintype "passive"))
      (node (ref "R49") (pin "2") (pinfunction "2_2") (pintype "passive"))
    )
    (net (code "94") (name "Net-(L16-G)") (class "Default")
      (node (ref "L16") (pin "3") (pinfunction "G_3") (pintype "passive"))
      (node (ref "R47") (pin "2") (pinfunction "2_2") (pintype "passive"))
    )
    (net (code "95") (name "Net-(L16-R)") (class "Default")
      (node (ref "L16") (pin "1") (pinfunction "R_1") (pintype "passive"))
      (node (ref "R45") (pin "2") (pinfunction "2_2") (pintype "passive"))
    )
    (net (code "96") (name "Net-(M-PD0)") (class "Default")
      (node (ref "M") (pin "25") (pinfunction "PD0_25") (pintype "passive"))
      (node (ref "Opto Counter1") (pin "3") (pinfunction "Co_3") (pintype "passive"))
      (node (ref "R48") (pin "1") (pinfunction "1_1") (pintype "passive"))
    )
    (net (code "97") (name "Net-(M-PD2)") (class "Default")
      (node (ref "M") (pin "27") (pinfunction "PD2_27") (pintype "passive"))
      (node (ref "P2") (pin "2") (pinfunction "2_2") (pintype "passive"))
    )
    (net (code "98") (name "Net-(M-PD3)") (class "Default")
      (node (ref "M") (pin "28") (pinfunction "PD3_28") (pintype "passive"))
      (node (ref "P2") (pin "1") (pinfunction "1_1") (pintype "passive"))
    )
    (net (code "99") (name "Net-(Opto Counter1-An)") (class "Default")
      (node (ref "Opto Counter1") (pin "1") (pinfunction "An_1") (pintype "passive"))
      (node (ref "R50") (pin "2") (pinfunction "2_2") (pintype "passive"))
    )
    (net (code "100") (name "Net-(S1-COMMON)") (class "Default")
      (node (ref "L_in1") (pin "2") (pinfunction "2_2") (pintype "passive"))
      (node (ref "S1") (pin "1") (pinfunction "COMMON_1") (pintype "passive"))
    )
    (net (code "101") (name "VCC") (class "Default")
      (node (ref "74541-1") (pin "20") (pinfunction "Vcc_20") (pintype "passive"))
      (node (ref "74541-2") (pin "20") (pinfunction "Vcc_20") (pintype "passive"))
      (node (ref "C1") (pin "1") (pinfunction "1_1") (pintype "passive"))
      (node (ref "L_in1") (pin "1") (pinfunction "1_1") (pintype "passive"))
      (node (ref "M") (pin "21") (pinfunction "VCC_21") (pintype "power_in"))
      (node (ref "M") (pin "52") (pinfunction "VCC_52") (pintype "power_in"))
      (node (ref "M") (pin "64") (pinfunction "AVCC_64") (pintype "power_in"))
      (node (ref "R48") (pin "2") (pinfunction "2_2") (pintype "passive"))
      (node (ref "R50") (pin "1") (pinfunction "1_1") (pintype "passive"))
    )
    (net (code "102") (name "unconnected-(M-AREF-Pad62)") (class "Default")
      (node (ref "M") (pin "62") (pinfunction "AREF_62") (pintype "passive"))
    )
    (net (code "103") (name "unconnected-(M-PB0-Pad10)") (class "Default")
      (node (ref "M") (pin "10") (pinfunction "PB0_10") (pintype "passive"))
    )
    (net (code "104") (name "unconnected-(M-PB2-Pad12)") (class "Default")
      (node (ref "M") (pin "12") (pinfunction "PB2_12") (pintype "passive"))
    )
    (net (code "105") (name "unconnected-(M-PB3-Pad13)") (class "Default")
      (node (ref "M") (pin "13") (pinfunction "PB3_13") (pintype "passive"))
    )
    (net (code "106") (name "unconnected-(M-PB4-Pad14)") (class "Default")
      (node (ref "M") (pin "14") (pinfunction "PB4_14") (pintype "passive"))
    )
    (net (code "107") (name "unconnected-(M-PB5-Pad15)") (class "Default")
      (node (ref "M") (pin "15") (pinfunction "PB5_15") (pintype "passive"))
    )
    (net (code "108") (name "unconnected-(M-PB7-Pad17)") (class "Default")
      (node (ref "M") (pin "17") (pinfunction "PB7_17") (pintype "passive"))
    )
    (net (code "109") (name "unconnected-(M-PD1-Pad26)") (class "Default")
      (node (ref "M") (pin "26") (pinfunction "PD1_26") (pintype "passive"))
    )
    (net (code "110") (name "unconnected-(M-PD4-Pad29)") (class "Default")
      (node (ref "M") (pin "29") (pinfunction "PD4_29") (pintype "passive"))
    )
    (net (code "111") (name "unconnected-(M-PD5-Pad30)") (class "Default")
      (node (ref "M") (pin "30") (pinfunction "PD5_30") (pintype "passive"))
    )
    (net (code "112") (name "unconnected-(M-PD6-Pad31)") (class "Default")
      (node (ref "M") (pin "31") (pinfunction "PD6_31") (pintype "passive"))
    )
    (net (code "113") (name "unconnected-(M-PD7-Pad32)") (class "Default")
      (node (ref "M") (pin "32") (pinfunction "PD7_32") (pintype "passive"))
    )
    (net (code "114") (name "unconnected-(M-PE2-Pad4)") (class "Default")
      (node (ref "M") (pin "4") (pinfunction "PE2_4") (pintype "passive"))
    )
    (net (code "115") (name "unconnected-(M-PE3-Pad5)") (class "Default")
      (node (ref "M") (pin "5") (pinfunction "PE3_5") (pintype "passive"))
    )
    (net (code "116") (name "unconnected-(M-PE6-Pad8)") (class "Default")
      (node (ref "M") (pin "8") (pinfunction "PE6_8") (pintype "passive"))
    )
    (net (code "117") (name "unconnected-(M-PE7-Pad9)") (class "Default")
      (node (ref "M") (pin "9") (pinfunction "PE7_9") (pintype "passive"))
    )
    (net (code "118") (name "unconnected-(M-PEN-Pad1)") (class "Default")
      (node (ref "M") (pin "1") (pinfunction "PEN_1") (pintype "passive"))
    )
    (net (code "119") (name "unconnected-(M-PF0-Pad61)") (class "Default")
      (node (ref "M") (pin "61") (pinfunction "PF0_61") (pintype "passive"))
    )
    (net (code "120") (name "unconnected-(M-PF1-Pad60)") (class "Default")
      (node (ref "M") (pin "60") (pinfunction "PF1_60") (pintype "passive"))
    )
    (net (code "121") (name "unconnected-(M-PF2-Pad59)") (class "Default")
      (node (ref "M") (pin "59") (pinfunction "PF2_59") (pintype "passive"))
    )
    (net (code "122") (name "unconnected-(M-PF3-Pad58)") (class "Default")
      (node (ref "M") (pin "58") (pinfunction "PF3_58") (pintype "passive"))
    )
    (net (code "123") (name "unconnected-(M-PF4-Pad57)") (class "Default")
      (node (ref "M") (pin "57") (pinfunction "PF4_57") (pintype "passive"))
    )
    (net (code "124") (name "unconnected-(M-PF5-Pad56)") (class "Default")
      (node (ref "M") (pin "56") (pinfunction "PF5_56") (pintype "passive"))
    )
    (net (code "125") (name "unconnected-(M-PF6-Pad55)") (class "Default")
      (node (ref "M") (pin "55") (pinfunction "PF6_55") (pintype "passive"))
    )
    (net (code "126") (name "unconnected-(M-PF7-Pad54)") (class "Default")
      (node (ref "M") (pin "54") (pinfunction "PF7_54") (pintype "passive"))
    )
    (net (code "127") (name "unconnected-(M-PG0-Pad33)") (class "Default")
      (node (ref "M") (pin "33") (pinfunction "PG0_33") (pintype "passive"))
    )
    (net (code "128") (name "unconnected-(M-PG3-Pad18)") (class "Default")
      (node (ref "M") (pin "18") (pinfunction "PG3_18") (pintype "passive"))
    )
    (net (code "129") (name "unconnected-(M-PG4-Pad19)") (class "Default")
      (node (ref "M") (pin "19") (pinfunction "PG4_19") (pintype "passive"))
    )
    (net (code "130") (name "unconnected-(M-XTAL1-Pad24)") (class "Default")
      (node (ref "M") (pin "24") (pinfunction "XTAL1_24") (pintype "passive"))
    )
    (net (code "131") (name "unconnected-(M-XTAL2-Pad23)") (class "Default")
      (node (ref "M") (pin "23") (pinfunction "XTAL2_23") (pintype "passive"))
    )
    (net (code "132") (name "unconnected-(P1-Pad2)") (class "Default")
      (node (ref "P1") (pin "2") (pinfunction "2_2") (pintype "passive"))
    )
    (net (code "133") (name "unconnected-(ULN-A3-Pad4)") (class "Default")
      (node (ref "ULN") (pin "4") (pinfunction "A3_4") (pintype "passive"))
    )
    (net (code "134") (name "unconnected-(ULN-A4-Pad5)") (class "Default")
      (node (ref "ULN") (pin "5") (pinfunction "A4_5") (pintype "passive"))
    )
    (net (code "135") (name "unconnected-(ULN-A5-Pad6)") (class "Default")
      (node (ref "ULN") (pin "6") (pinfunction "A5_6") (pintype "passive"))
    )
    (net (code "136") (name "unconnected-(ULN-A6-Pad7)") (class "Default")
      (node (ref "ULN") (pin "7") (pinfunction "A6_7") (pintype "passive"))
    )
    (net (code "137") (name "unconnected-(ULN-Y3-Pad13)") (class "Default")
      (node (ref "ULN") (pin "13") (pinfunction "Y3_13") (pintype "passive"))
    )
    (net (code "138") (name "unconnected-(ULN-Y4-Pad12)") (class "Default")
      (node (ref "ULN") (pin "12") (pinfunction "Y4_12") (pintype "passive"))
    )
    (net (code "139") (name "unconnected-(ULN-Y5-Pad11)") (class "Default")
      (node (ref "ULN") (pin "11") (pinfunction "Y5_11") (pintype "passive"))
    )
    (net (code "140") (name "unconnected-(ULN-Y6-Pad10)") (class "Default")
      (node (ref "ULN") (pin "10") (pinfunction "Y6_10") (pintype "passive"))
    )
    (net (code "141") (name "unconnected-(ULN-Y7-Pad9)") (class "Default")
      (node (ref "ULN") (pin "9") (pinfunction "Y7_9") (pintype "passive"))
    )
  )
)
